# ElectronSheriff.net
KiCad netlist of a schematic drawn in EAGLE
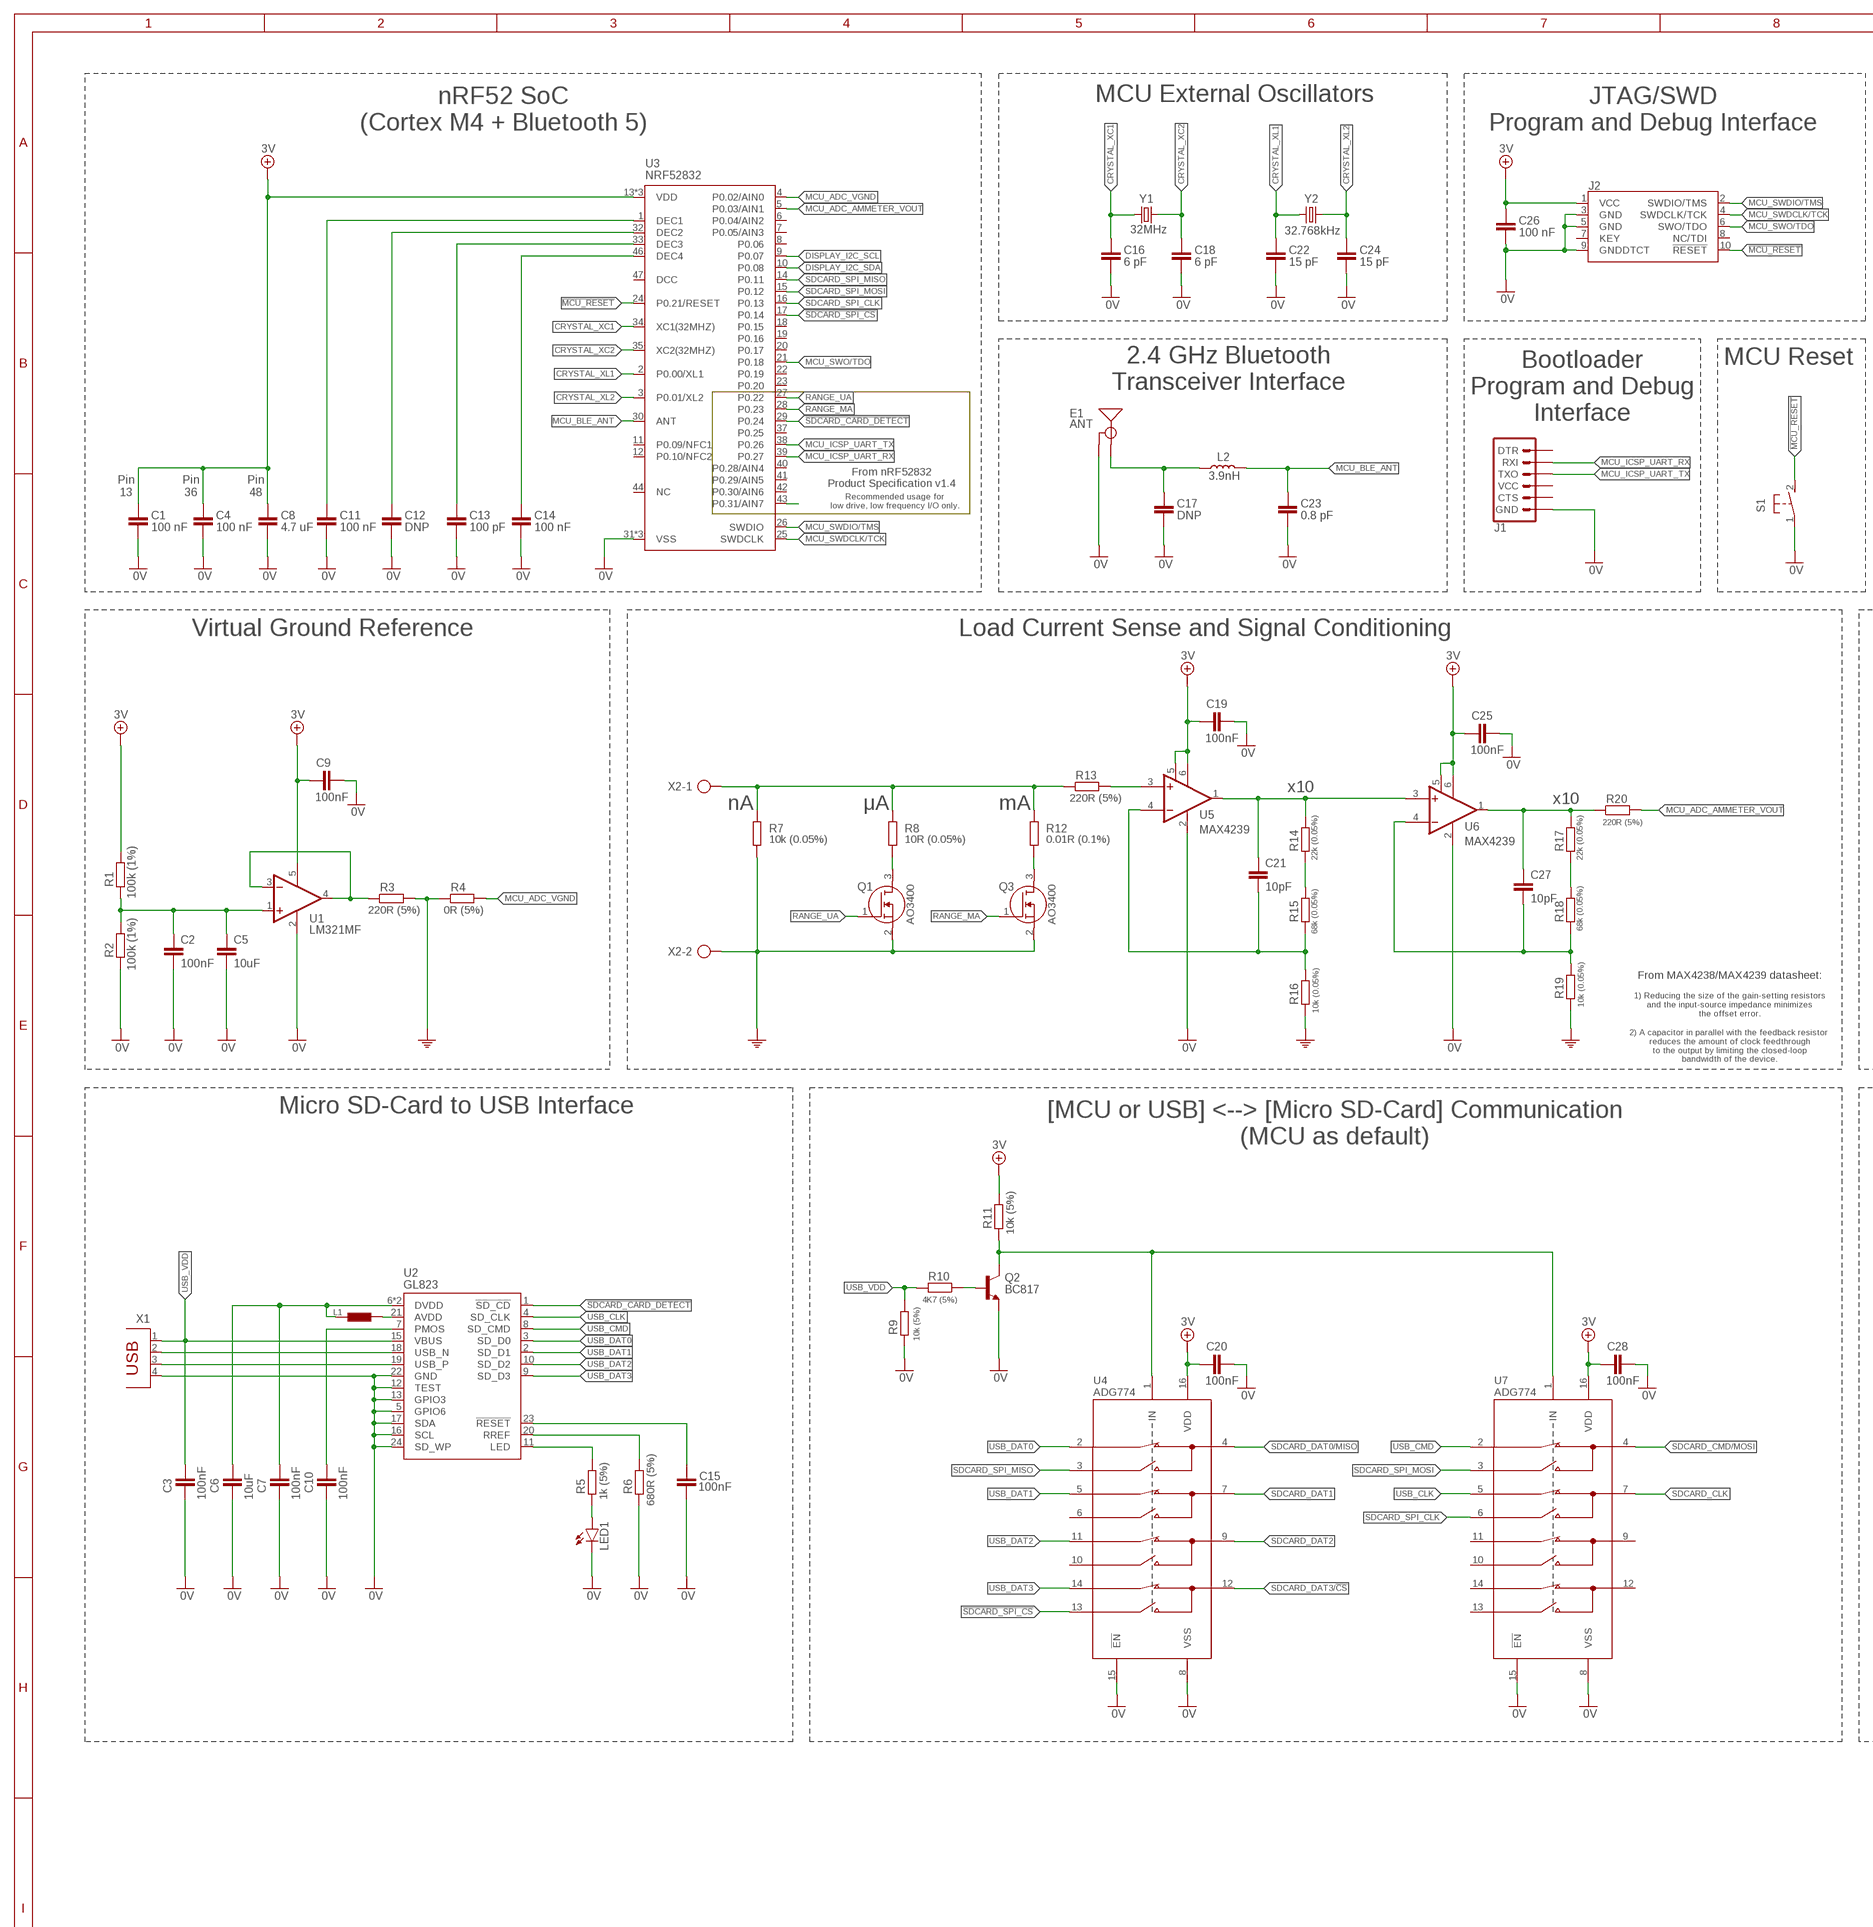
[diagram p0: schematic, sheet 1, part 1 of 2]
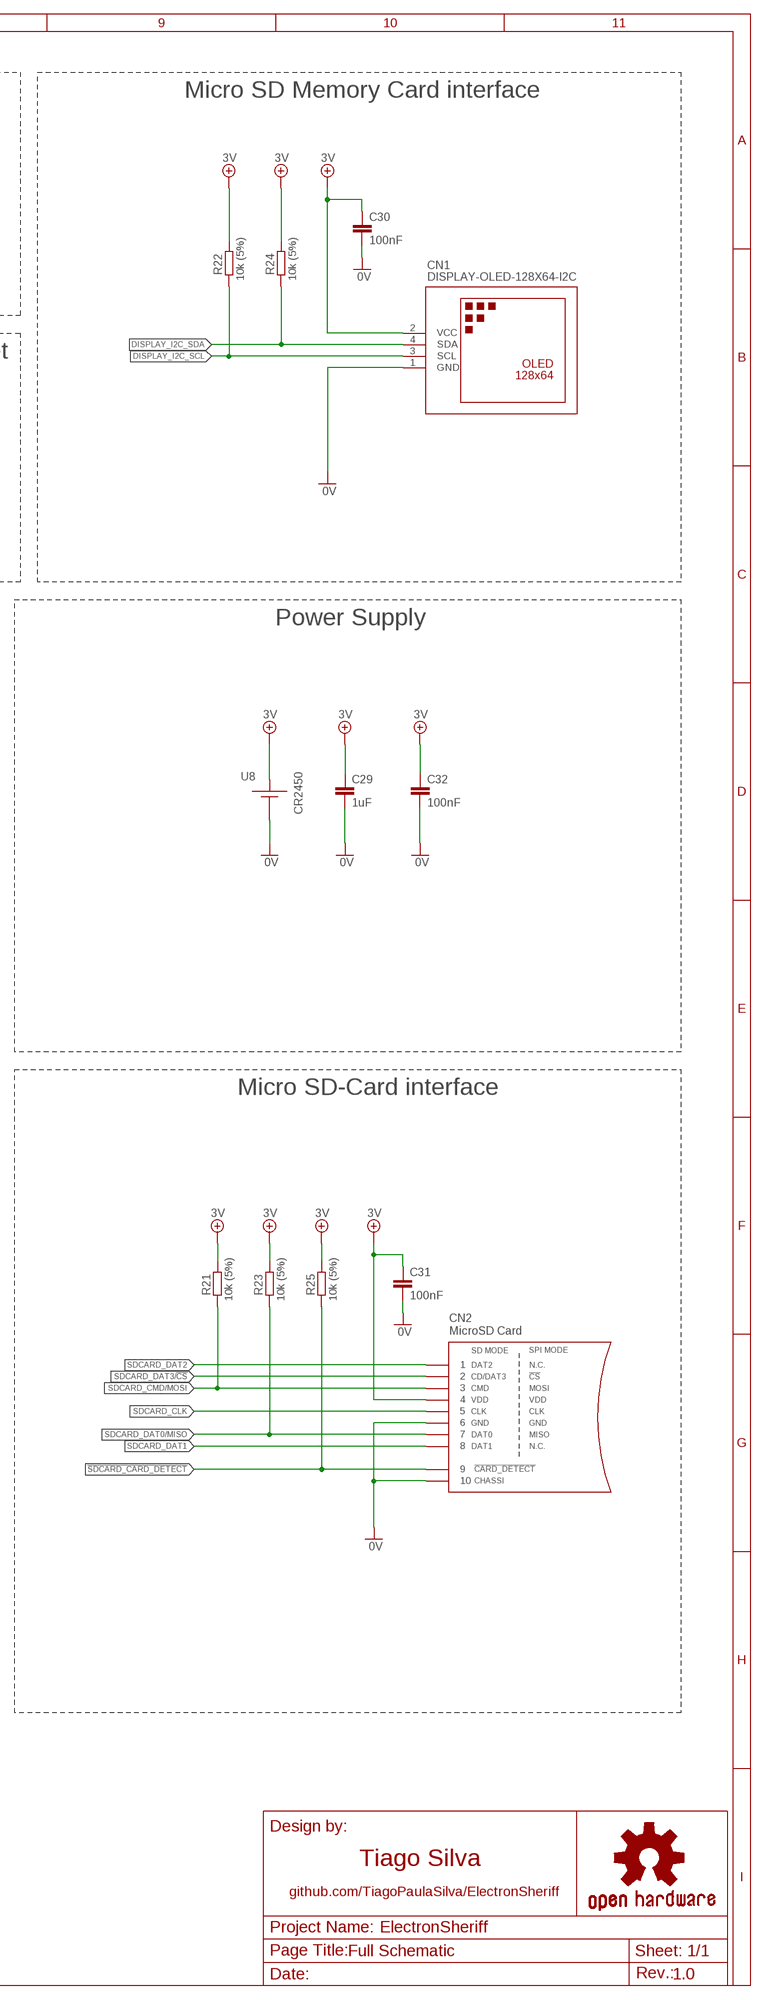
[diagram p1: schematic, sheet 1, part 2 of 2]

(export (version "E")
  (design (tool "Eeschema 10.0.6"))
  (components
    (comp (ref "C1")
      (value "100 nF")
      (footprint "eagle-import:C0603")
      (libsource (lib "eagle-import") (part "C-EUC0603"))
    )
    (comp (ref "C2")
      (value "100nF")
      (footprint "eagle-import:C0603")
      (libsource (lib "eagle-import") (part "C-EUC0603"))
    )
    (comp (ref "C3")
      (value "100nF")
      (footprint "eagle-import:C0603")
      (libsource (lib "eagle-import") (part "C-EUC0603"))
    )
    (comp (ref "C4")
      (value "100 nF")
      (footprint "eagle-import:C0603")
      (libsource (lib "eagle-import") (part "C-EUC0603"))
    )
    (comp (ref "C5")
      (value "10uF")
      (footprint "eagle-import:C0805")
      (libsource (lib "eagle-import") (part "C-EUC0805"))
    )
    (comp (ref "C6")
      (value "10uF")
      (footprint "eagle-import:C0603")
      (libsource (lib "eagle-import") (part "C-EUC0603"))
    )
    (comp (ref "C7")
      (value "100nF")
      (footprint "eagle-import:C0603")
      (libsource (lib "eagle-import") (part "C-EUC0603"))
    )
    (comp (ref "C8")
      (value "4.7 uF")
      (footprint "eagle-import:C0603")
      (libsource (lib "eagle-import") (part "C-EUC0603"))
    )
    (comp (ref "C9")
      (value "100nF")
      (footprint "eagle-import:C0603")
      (libsource (lib "eagle-import") (part "C-EUC0603"))
    )
    (comp (ref "C10")
      (value "100nF")
      (footprint "eagle-import:C0603")
      (libsource (lib "eagle-import") (part "C-EUC0603"))
    )
    (comp (ref "C11")
      (value "100 nF")
      (footprint "eagle-import:C0603")
      (libsource (lib "eagle-import") (part "C-EUC0603"))
    )
    (comp (ref "C12")
      (value "DNP")
      (footprint "eagle-import:C0603")
      (libsource (lib "eagle-import") (part "C-EUC0603"))
    )
    (comp (ref "C13")
      (value "100 pF")
      (footprint "eagle-import:C0603")
      (libsource (lib "eagle-import") (part "C-EUC0603"))
    )
    (comp (ref "C14")
      (value "100 nF")
      (footprint "eagle-import:C0603")
      (libsource (lib "eagle-import") (part "C-EUC0603"))
    )
    (comp (ref "C15")
      (value "100nF")
      (footprint "eagle-import:C0603")
      (libsource (lib "eagle-import") (part "C-EUC0603"))
    )
    (comp (ref "C16")
      (value "6 pF")
      (footprint "eagle-import:C0603")
      (libsource (lib "eagle-import") (part "C-EUC0603"))
    )
    (comp (ref "C17")
      (value "DNP")
      (footprint "eagle-import:C0603")
      (libsource (lib "eagle-import") (part "C-EUC0603"))
    )
    (comp (ref "C18")
      (value "6 pF")
      (footprint "eagle-import:C0603")
      (libsource (lib "eagle-import") (part "C-EUC0603"))
    )
    (comp (ref "C19")
      (value "100nF")
      (footprint "eagle-import:C0603")
      (libsource (lib "eagle-import") (part "C-EUC0603"))
    )
    (comp (ref "C20")
      (value "100nF")
      (footprint "eagle-import:C0603")
      (libsource (lib "eagle-import") (part "C-EUC0603"))
    )
    (comp (ref "C21")
      (value "10pF")
      (footprint "eagle-import:C0603")
      (libsource (lib "eagle-import") (part "C-EUC0603"))
    )
    (comp (ref "C22")
      (value "15 pF")
      (footprint "eagle-import:C0603")
      (libsource (lib "eagle-import") (part "C-EUC0603"))
    )
    (comp (ref "C23")
      (value "0.8 pF")
      (footprint "eagle-import:C0603")
      (libsource (lib "eagle-import") (part "C-EUC0603"))
    )
    (comp (ref "C24")
      (value "15 pF")
      (footprint "eagle-import:C0603")
      (libsource (lib "eagle-import") (part "C-EUC0603"))
    )
    (comp (ref "C25")
      (value "100nF")
      (footprint "eagle-import:C0603")
      (libsource (lib "eagle-import") (part "C-EUC0603"))
    )
    (comp (ref "C26")
      (value "100 nF")
      (footprint "eagle-import:C0603")
      (libsource (lib "eagle-import") (part "C-EUC0603"))
    )
    (comp (ref "C27")
      (value "10pF")
      (footprint "eagle-import:C0603")
      (libsource (lib "eagle-import") (part "C-EUC0603"))
    )
    (comp (ref "C28")
      (value "100nF")
      (footprint "eagle-import:C0603")
      (libsource (lib "eagle-import") (part "C-EUC0603"))
    )
    (comp (ref "C29")
      (value "1uF")
      (footprint "eagle-import:C0603")
      (libsource (lib "eagle-import") (part "C-EUC0603"))
    )
    (comp (ref "C30")
      (value "100nF")
      (footprint "eagle-import:C0603")
      (libsource (lib "eagle-import") (part "C-EUC0603"))
    )
    (comp (ref "C31")
      (value "100nF")
      (footprint "eagle-import:C0603")
      (libsource (lib "eagle-import") (part "C-EUC0603"))
    )
    (comp (ref "C32")
      (value "100nF")
      (footprint "eagle-import:C0603")
      (libsource (lib "eagle-import") (part "C-EUC0603"))
    )
    (comp (ref "CN1")
      (value "DISPLAY-OLED-128X64-I2C")
      (footprint "eagle-import:DISPLAY-OLED-128X64-I2C")
      (libsource (lib "eagle-import") (part "DISPLAY-OLED-128X64-I2C"))
    )
    (comp (ref "CN2")
      (value "MicroSD Card")
      (footprint "eagle-import:MICROSD-PUSH-OUT")
      (libsource (lib "eagle-import") (part "MICROSD-PUSH-OUT"))
    )
    (comp (ref "E1")
      (value "ANT")
      (footprint "eagle-import:TRACE_ANTENNA_2.4GHZ_15.2MM")
      (libsource (lib "eagle-import") (part "ANTENNA-GROUNDEDTRACE-15.2MM"))
    )
    (comp (ref "J1")
      (value "ARDUINO_SERIAL_PROGRAMPTH")
      (footprint "eagle-import:1X06")
      (libsource (lib "eagle-import") (part "ARDUINO_SERIAL_PROGRAMPTH"))
    )
    (comp (ref "J2")
      (value "CORTEX_DEBUGPTH")
      (footprint "eagle-import:2X5-PTH-1.27MM")
      (libsource (lib "eagle-import") (part "CORTEX_DEBUGPTH"))
    )
    (comp (ref "L1")
      (value "BLM15HB221SN1")
      (footprint "eagle-import:0402")
      (libsource (lib "eagle-import") (part "BLM15HB221SN1"))
    )
    (comp (ref "L2")
      (value "3.9nH")
      (footprint "eagle-import:0402")
      (libsource (lib "eagle-import") (part "INDUCTOR-0402-3.9NH"))
    )
    (comp (ref "LED1")
      (value "LEDCHIPLED_0603")
      (footprint "eagle-import:CHIPLED_0603")
      (libsource (lib "eagle-import") (part "LEDCHIPLED_0603"))
    )
    (comp (ref "Q1")
      (value "AO3400")
      (footprint "eagle-import:SOT95P280X125-3N")
      (libsource (lib "eagle-import") (part "AO3400"))
    )
    (comp (ref "Q2")
      (value "BC817")
      (footprint "eagle-import:SOT23-BEC")
      (libsource (lib "eagle-import") (part "BC817SMD-16LT1"))
    )
    (comp (ref "Q3")
      (value "AO3400")
      (footprint "eagle-import:SOT95P280X125-3N")
      (libsource (lib "eagle-import") (part "AO3400"))
    )
    (comp (ref "R1")
      (value "100k (1%)")
      (footprint "eagle-import:R0603")
      (libsource (lib "eagle-import") (part "R-EU_R0603"))
    )
    (comp (ref "R2")
      (value "100k (1%)")
      (footprint "eagle-import:R0603")
      (libsource (lib "eagle-import") (part "R-EU_R0603"))
    )
    (comp (ref "R3")
      (value "220R (5%)")
      (footprint "eagle-import:R0603")
      (libsource (lib "eagle-import") (part "R-EU_R0603"))
    )
    (comp (ref "R4")
      (value "0R (5%)")
      (footprint "eagle-import:R0603")
      (libsource (lib "eagle-import") (part "R-EU_R0603"))
    )
    (comp (ref "R5")
      (value "1k (5%)")
      (footprint "eagle-import:R0603")
      (libsource (lib "eagle-import") (part "R-EU_R0603"))
    )
    (comp (ref "R6")
      (value "680R (5%)")
      (footprint "eagle-import:R0603")
      (libsource (lib "eagle-import") (part "R-EU_R0603"))
    )
    (comp (ref "R7")
      (value "10k (0.05%)")
      (footprint "eagle-import:R0603")
      (libsource (lib "eagle-import") (part "R-EU_R0603"))
    )
    (comp (ref "R8")
      (value "10R (0.05%)")
      (footprint "eagle-import:R0603")
      (libsource (lib "eagle-import") (part "R-EU_R0603"))
    )
    (comp (ref "R9")
      (value "10k (5%)")
      (footprint "eagle-import:R0603")
      (libsource (lib "eagle-import") (part "R-EU_R0603"))
    )
    (comp (ref "R10")
      (value "4K7 (5%)")
      (footprint "eagle-import:R0603")
      (libsource (lib "eagle-import") (part "R-EU_R0603"))
    )
    (comp (ref "R11")
      (value "10k (5%)")
      (footprint "eagle-import:R0603")
      (libsource (lib "eagle-import") (part "R-EU_R0603"))
    )
    (comp (ref "R12")
      (value "0.01R (0.1%)")
      (footprint "eagle-import:R0603")
      (libsource (lib "eagle-import") (part "R-EU_R0603"))
    )
    (comp (ref "R13")
      (value "220R (5%)")
      (footprint "eagle-import:R0603")
      (libsource (lib "eagle-import") (part "R-EU_R0603"))
    )
    (comp (ref "R14")
      (value "22k (0.05%)")
      (footprint "eagle-import:R0603")
      (libsource (lib "eagle-import") (part "R-EU_R0603"))
    )
    (comp (ref "R15")
      (value "68k (0.05%)")
      (footprint "eagle-import:R0603")
      (libsource (lib "eagle-import") (part "R-EU_R0603"))
    )
    (comp (ref "R16")
      (value "10k (0.05%)")
      (footprint "eagle-import:R0603")
      (libsource (lib "eagle-import") (part "R-EU_R0603"))
    )
    (comp (ref "R17")
      (value "22k (0.05%)")
      (footprint "eagle-import:R0603")
      (libsource (lib "eagle-import") (part "R-EU_R0603"))
    )
    (comp (ref "R18")
      (value "68k (0.05%)")
      (footprint "eagle-import:R0603")
      (libsource (lib "eagle-import") (part "R-EU_R0603"))
    )
    (comp (ref "R19")
      (value "10k (0.05%)")
      (footprint "eagle-import:R0603")
      (libsource (lib "eagle-import") (part "R-EU_R0603"))
    )
    (comp (ref "R20")
      (value "220R (5%)")
      (footprint "eagle-import:R0603")
      (libsource (lib "eagle-import") (part "R-EU_R0603"))
    )
    (comp (ref "R21")
      (value "10k (5%)")
      (footprint "eagle-import:R0603")
      (libsource (lib "eagle-import") (part "R-EU_R0603"))
    )
    (comp (ref "R22")
      (value "10k (5%)")
      (footprint "eagle-import:R0603")
      (libsource (lib "eagle-import") (part "R-EU_R0603"))
    )
    (comp (ref "R23")
      (value "10k (5%)")
      (footprint "eagle-import:R0603")
      (libsource (lib "eagle-import") (part "R-EU_R0603"))
    )
    (comp (ref "R24")
      (value "10k (5%)")
      (footprint "eagle-import:R0603")
      (libsource (lib "eagle-import") (part "R-EU_R0603"))
    )
    (comp (ref "R25")
      (value "10k (5%)")
      (footprint "eagle-import:R0603")
      (libsource (lib "eagle-import") (part "R-EU_R0603"))
    )
    (comp (ref "S1")
      (value "DTSM-3")
      (footprint "eagle-import:DTSM-3")
      (libsource (lib "eagle-import") (part "DTSM-3"))
    )
    (comp (ref "U1")
      (value "LM321MF")
      (footprint "eagle-import:SOT23-5")
      (libsource (lib "eagle-import") (part "LM321?MF"))
    )
    (comp (ref "U2")
      (value "GL823")
      (footprint "eagle-import:SSOP24")
      (libsource (lib "eagle-import") (part "GL823(B)HG"))
    )
    (comp (ref "U3")
      (value "NRF52832")
      (footprint "eagle-import:QFN48-6X6MM")
      (libsource (lib "eagle-import") (part "NRF52832"))
    )
    (comp (ref "U4")
      (value "ADG774")
      (footprint "eagle-import:SOIC127P600X175-16N")
      (libsource (lib "eagle-import") (part "ADG774"))
    )
    (comp (ref "U5")
      (value "MAX4239")
      (footprint "eagle-import:SOT95P280X145-6N")
      (fields (field (name "MF") "Maxim Integrated") (field (name "MP") "MAX4239AUT+T"))
      (libsource (lib "eagle-import") (part "MAX4239AUTT"))
    )
    (comp (ref "U6")
      (value "MAX4239")
      (footprint "eagle-import:SOT95P280X145-6N")
      (fields (field (name "MF") "Maxim Integrated") (field (name "MP") "MAX4239AUT+T"))
      (libsource (lib "eagle-import") (part "MAX4239AUTT"))
    )
    (comp (ref "U7")
      (value "ADG774")
      (footprint "eagle-import:SOIC127P600X175-16N")
      (libsource (lib "eagle-import") (part "ADG774"))
    )
    (comp (ref "U8")
      (value "CR2450")
      (footprint "eagle-import:1053")
      (fields
        (field (name "MANUFACTURER_PART_NUMBER") "1053")
        (field (name "MOUSER_PART_NUMBER") "534-1053-BH")
      )
      (libsource (lib "eagle-import") (part "1053"))
    )
    (comp (ref "X1")
      (value "PN87520")
      (footprint "eagle-import:PN87520")
      (libsource (lib "eagle-import") (part "PN87520"))
    )
    (comp (ref "X2")
      (value "AK500/2-H")
      (footprint "eagle-import:AK500_2-H")
      (libsource (lib "eagle-import") (part "AK500/2-H"))
    )
    (comp (ref "Y1")
      (value "32MHz")
      (footprint "eagle-import:CRYSTAL-SMD-2.0X1.6MM")
      (libsource (lib "eagle-import") (part "CRYSTAL-32MHZ-SMD-2.0X1.6MM"))
    )
    (comp (ref "Y2")
      (value "32.768kHz")
      (footprint "eagle-import:CRYSTAL-SMD-3.2X1.5MM")
      (libsource (lib "eagle-import") (part "CRYSTAL-32.768KHZSMD-3.2X1.5"))
    )
  )
  (nets
    (net (code "1") (name "/SDCARD_DAT3{slash}~{CS}") (class "Default")
      (node (ref "CN2") (pin "2") (pinfunction "2_2") (pintype "bidirectional"))
      (node (ref "U4") (pin "12") (pinfunction "D4_12") (pintype "bidirectional"))
    )
    (net (code "2") (name "/~{MCU_RESET}") (class "Default")
      (node (ref "J2") (pin "10") (pinfunction "~{RESET}_10") (pintype "bidirectional"))
      (node (ref "S1") (pin "2") (pinfunction "2_2") (pintype "passive"))
      (node (ref "U3") (pin "24") (pinfunction "P0.21/RESET_24") (pintype "bidirectional"))
    )
    (net (code "3") (name "/~{SDCARD_CARD_DETECT}") (class "Default")
      (node (ref "CN2") (pin "9") (pinfunction "9_9") (pintype "bidirectional"))
      (node (ref "R25") (pin "1") (pinfunction "1_1") (pintype "passive"))
      (node (ref "U2") (pin "1") (pinfunction "~{SD_CD}_1") (pintype "input"))
      (node (ref "U3") (pin "29") (pinfunction "P0.24_29") (pintype "bidirectional"))
    )
    (net (code "4") (name "/~{SDCARD_SPI_CS}") (class "Default")
      (node (ref "U3") (pin "17") (pinfunction "P0.14_17") (pintype "bidirectional"))
      (node (ref "U4") (pin "13") (pinfunction "S4B_13") (pintype "bidirectional"))
    )
    (net (code "5") (name "0V") (class "Default")
      (node (ref "C1") (pin "2") (pinfunction "2_2") (pintype "passive"))
      (node (ref "C10") (pin "1") (pinfunction "1_1") (pintype "passive"))
      (node (ref "C11") (pin "2") (pinfunction "2_2") (pintype "passive"))
      (node (ref "C12") (pin "2") (pinfunction "2_2") (pintype "passive"))
      (node (ref "C13") (pin "2") (pinfunction "2_2") (pintype "passive"))
      (node (ref "C14") (pin "2") (pinfunction "2_2") (pintype "passive"))
      (node (ref "C15") (pin "1") (pinfunction "1_1") (pintype "passive"))
      (node (ref "C16") (pin "2") (pinfunction "2_2") (pintype "passive"))
      (node (ref "C17") (pin "2") (pinfunction "2_2") (pintype "passive"))
      (node (ref "C18") (pin "2") (pinfunction "2_2") (pintype "passive"))
      (node (ref "C19") (pin "2") (pinfunction "2_2") (pintype "passive"))
      (node (ref "C2") (pin "2") (pinfunction "2_2") (pintype "passive"))
      (node (ref "C20") (pin "2") (pinfunction "2_2") (pintype "passive"))
      (node (ref "C22") (pin "2") (pinfunction "2_2") (pintype "passive"))
      (node (ref "C23") (pin "2") (pinfunction "2_2") (pintype "passive"))
      (node (ref "C24") (pin "2") (pinfunction "2_2") (pintype "passive"))
      (node (ref "C25") (pin "2") (pinfunction "2_2") (pintype "passive"))
      (node (ref "C26") (pin "2") (pinfunction "2_2") (pintype "passive"))
      (node (ref "C28") (pin "2") (pinfunction "2_2") (pintype "passive"))
      (node (ref "C29") (pin "2") (pinfunction "2_2") (pintype "passive"))
      (node (ref "C3") (pin "1") (pinfunction "1_1") (pintype "passive"))
      (node (ref "C30") (pin "2") (pinfunction "2_2") (pintype "passive"))
      (node (ref "C31") (pin "2") (pinfunction "2_2") (pintype "passive"))
      (node (ref "C32") (pin "2") (pinfunction "2_2") (pintype "passive"))
      (node (ref "C4") (pin "2") (pinfunction "2_2") (pintype "passive"))
      (node (ref "C5") (pin "2") (pinfunction "2_2") (pintype "passive"))
      (node (ref "C6") (pin "1") (pinfunction "1_1") (pintype "passive"))
      (node (ref "C7") (pin "1") (pinfunction "1_1") (pintype "passive"))
      (node (ref "C8") (pin "2") (pinfunction "2_2") (pintype "passive"))
      (node (ref "C9") (pin "2") (pinfunction "2_2") (pintype "passive"))
      (node (ref "CN1") (pin "1") (pinfunction "GND_1") (pintype "power_in"))
      (node (ref "CN2") (pin "6") (pinfunction "6_6") (pintype "bidirectional"))
      (node (ref "CN2") (pin "G1") (pinfunction "10_G1") (pintype "bidirectional"))
      (node (ref "CN2") (pin "G2") (pinfunction "10_G2") (pintype "bidirectional"))
      (node (ref "CN2") (pin "G3") (pinfunction "10_G3") (pintype "bidirectional"))
      (node (ref "CN2") (pin "G4") (pinfunction "10_G4") (pintype "bidirectional"))
      (node (ref "E1") (pin "GND") (pinfunction "GND_GND") (pintype "bidirectional"))
      (node (ref "J1") (pin "6") (pinfunction "GND_6") (pintype "passive"))
      (node (ref "J2") (pin "3") (pinfunction "GND_3") (pintype "bidirectional"))
      (node (ref "J2") (pin "5") (pinfunction "GND_5") (pintype "bidirectional"))
      (node (ref "J2") (pin "9") (pinfunction "GNDDTCT_9") (pintype "bidirectional"))
      (node (ref "LED1") (pin "C") (pinfunction "C_C") (pintype "passive"))
      (node (ref "Q2") (pin "E") (pinfunction "E_E") (pintype "passive"))
      (node (ref "R2") (pin "1") (pinfunction "1_1") (pintype "passive"))
      (node (ref "R6") (pin "2") (pinfunction "2_2") (pintype "passive"))
      (node (ref "R9") (pin "2") (pinfunction "2_2") (pintype "passive"))
      (node (ref "S1") (pin "1") (pinfunction "1_1") (pintype "passive"))
      (node (ref "U1") (pin "2") (pinfunction "V-_2") (pintype "power_in"))
      (node (ref "U2") (pin "12") (pinfunction "TEST_12") (pintype "input"))
      (node (ref "U2") (pin "13") (pinfunction "GPIO3_13") (pintype "bidirectional"))
      (node (ref "U2") (pin "16") (pinfunction "SCL_16") (pintype "bidirectional"))
      (node (ref "U2") (pin "17") (pinfunction "SDA_17") (pintype "bidirectional"))
      (node (ref "U2") (pin "22") (pinfunction "GND_22") (pintype "power_in"))
      (node (ref "U2") (pin "24") (pinfunction "SD_WP_24") (pintype "input"))
      (node (ref "U2") (pin "5") (pinfunction "GPIO6_5") (pintype "bidirectional"))
      (node (ref "U3") (pin "31") (pinfunction "VSS_31") (pintype "bidirectional"))
      (node (ref "U3") (pin "45") (pinfunction "VSS_45") (pintype "bidirectional"))
      (node (ref "U3") (pin "EP") (pinfunction "VSS_EP") (pintype "bidirectional"))
      (node (ref "U4") (pin "15") (pinfunction "~{EN}_15") (pintype "bidirectional"))
      (node (ref "U4") (pin "8") (pinfunction "VSS_8") (pintype "bidirectional"))
      (node (ref "U5") (pin "2") (pinfunction "GND_2") (pintype "power_in"))
      (node (ref "U6") (pin "2") (pinfunction "GND_2") (pintype "power_in"))
      (node (ref "U7") (pin "15") (pinfunction "~{EN}_15") (pintype "bidirectional"))
      (node (ref "U7") (pin "8") (pinfunction "VSS_8") (pintype "bidirectional"))
      (node (ref "U8") (pin "1") (pinfunction "GND_1") (pintype "power_in"))
      (node (ref "X1") (pin "4") (pinfunction "4_4") (pintype "passive"))
    )
    (net (code "6") (name "3V") (class "Default")
      (node (ref "C1") (pin "1") (pinfunction "1_1") (pintype "passive"))
      (node (ref "C19") (pin "1") (pinfunction "1_1") (pintype "passive"))
      (node (ref "C20") (pin "1") (pinfunction "1_1") (pintype "passive"))
      (node (ref "C25") (pin "1") (pinfunction "1_1") (pintype "passive"))
      (node (ref "C26") (pin "1") (pinfunction "1_1") (pintype "passive"))
      (node (ref "C28") (pin "1") (pinfunction "1_1") (pintype "passive"))
      (node (ref "C29") (pin "1") (pinfunction "1_1") (pintype "passive"))
      (node (ref "C30") (pin "1") (pinfunction "1_1") (pintype "passive"))
      (node (ref "C31") (pin "1") (pinfunction "1_1") (pintype "passive"))
      (node (ref "C32") (pin "1") (pinfunction "1_1") (pintype "passive"))
      (node (ref "C4") (pin "1") (pinfunction "1_1") (pintype "passive"))
      (node (ref "C8") (pin "1") (pinfunction "1_1") (pintype "passive"))
      (node (ref "C9") (pin "1") (pinfunction "1_1") (pintype "passive"))
      (node (ref "CN1") (pin "2") (pinfunction "VCC_2") (pintype "power_in"))
      (node (ref "CN2") (pin "4") (pinfunction "4_4") (pintype "bidirectional"))
      (node (ref "J2") (pin "1") (pinfunction "VCC_1") (pintype "bidirectional"))
      (node (ref "R1") (pin "2") (pinfunction "2_2") (pintype "passive"))
      (node (ref "R11") (pin "2") (pinfunction "2_2") (pintype "passive"))
      (node (ref "R21") (pin "2") (pinfunction "2_2") (pintype "passive"))
      (node (ref "R22") (pin "2") (pinfunction "2_2") (pintype "passive"))
      (node (ref "R23") (pin "2") (pinfunction "2_2") (pintype "passive"))
      (node (ref "R24") (pin "2") (pinfunction "2_2") (pintype "passive"))
      (node (ref "R25") (pin "2") (pinfunction "2_2") (pintype "passive"))
      (node (ref "U1") (pin "5") (pinfunction "V+_5") (pintype "power_in"))
      (node (ref "U3") (pin "13") (pinfunction "VDD_13") (pintype "bidirectional"))
      (node (ref "U3") (pin "36") (pinfunction "VDD_36") (pintype "bidirectional"))
      (node (ref "U3") (pin "48") (pinfunction "VDD_48") (pintype "bidirectional"))
      (node (ref "U4") (pin "16") (pinfunction "VDD_16") (pintype "bidirectional"))
      (node (ref "U5") (pin "5") (pinfunction "~{SHDN}_5") (pintype "input"))
      (node (ref "U5") (pin "6") (pinfunction "VCC_6") (pintype "power_in"))
      (node (ref "U6") (pin "5") (pinfunction "~{SHDN}_5") (pintype "input"))
      (node (ref "U6") (pin "6") (pinfunction "VCC_6") (pintype "power_in"))
      (node (ref "U7") (pin "16") (pinfunction "VDD_16") (pintype "bidirectional"))
      (node (ref "U8") (pin "2") (pinfunction "3V_2") (pintype "power_in"))
    )
    (net (code "7") (name "CRYSTAL_XC1") (class "Default")
      (node (ref "C16") (pin "1") (pinfunction "1_1") (pintype "passive"))
      (node (ref "U3") (pin "34") (pinfunction "XC1(32MHZ)_34") (pintype "bidirectional"))
      (node (ref "Y1") (pin "3") (pinfunction "2_3") (pintype "passive"))
    )
    (net (code "8") (name "CRYSTAL_XC2") (class "Default")
      (node (ref "C18") (pin "1") (pinfunction "1_1") (pintype "passive"))
      (node (ref "U3") (pin "35") (pinfunction "XC2(32MHZ)_35") (pintype "bidirectional"))
      (node (ref "Y1") (pin "1") (pinfunction "1_1") (pintype "passive"))
    )
    (net (code "9") (name "CRYSTAL_XL1") (class "Default")
      (node (ref "C22") (pin "1") (pinfunction "1_1") (pintype "passive"))
      (node (ref "U3") (pin "2") (pinfunction "P0.00/XL1_2") (pintype "bidirectional"))
      (node (ref "Y2") (pin "P$2") (pinfunction "2_P$2") (pintype "passive"))
    )
    (net (code "10") (name "CRYSTAL_XL2") (class "Default")
      (node (ref "C24") (pin "1") (pinfunction "1_1") (pintype "passive"))
      (node (ref "U3") (pin "3") (pinfunction "P0.01/XL2_3") (pintype "bidirectional"))
      (node (ref "Y2") (pin "P$1") (pinfunction "1_P$1") (pintype "passive"))
    )
    (net (code "11") (name "DISPLAY_I2C_SCL") (class "Default")
      (node (ref "CN1") (pin "3") (pinfunction "SCL_3") (pintype "bidirectional"))
      (node (ref "R22") (pin "1") (pinfunction "1_1") (pintype "passive"))
      (node (ref "U3") (pin "9") (pinfunction "P0.07_9") (pintype "bidirectional"))
    )
    (net (code "12") (name "DISPLAY_I2C_SDA") (class "Default")
      (node (ref "CN1") (pin "4") (pinfunction "SDA_4") (pintype "bidirectional"))
      (node (ref "R24") (pin "1") (pinfunction "1_1") (pintype "passive"))
      (node (ref "U3") (pin "10") (pinfunction "P0.08_10") (pintype "bidirectional"))
    )
    (net (code "13") (name "MCU_ADC_AMMETER_VOUT") (class "Default")
      (node (ref "R20") (pin "2") (pinfunction "2_2") (pintype "passive"))
      (node (ref "U3") (pin "5") (pinfunction "P0.03/AIN1_5") (pintype "bidirectional"))
    )
    (net (code "14") (name "MCU_ADC_VGND") (class "Default")
      (node (ref "R4") (pin "2") (pinfunction "2_2") (pintype "passive"))
      (node (ref "U3") (pin "4") (pinfunction "P0.02/AIN0_4") (pintype "bidirectional"))
    )
    (net (code "15") (name "MCU_BLE_ANT") (class "Default")
      (node (ref "C23") (pin "1") (pinfunction "1_1") (pintype "passive"))
      (node (ref "L2") (pin "2") (pinfunction "2_2") (pintype "passive"))
      (node (ref "U3") (pin "30") (pinfunction "ANT_30") (pintype "bidirectional"))
    )
    (net (code "16") (name "MCU_ICSP_UART_RX") (class "Default")
      (node (ref "J1") (pin "2") (pinfunction "RXI_2") (pintype "passive"))
      (node (ref "U3") (pin "39") (pinfunction "P0.27_39") (pintype "bidirectional"))
    )
    (net (code "17") (name "MCU_ICSP_UART_TX") (class "Default")
      (node (ref "J1") (pin "3") (pinfunction "TXO_3") (pintype "passive"))
      (node (ref "U3") (pin "38") (pinfunction "P0.26_38") (pintype "bidirectional"))
    )
    (net (code "18") (name "MCU_SWDCLK{slash}TCK") (class "Default")
      (node (ref "J2") (pin "4") (pinfunction "SWDCLK/TCK_4") (pintype "bidirectional"))
      (node (ref "U3") (pin "25") (pinfunction "SWDCLK_25") (pintype "bidirectional"))
    )
    (net (code "19") (name "MCU_SWDIO{slash}TMS") (class "Default")
      (node (ref "J2") (pin "2") (pinfunction "SWDIO/TMS_2") (pintype "bidirectional"))
      (node (ref "U3") (pin "26") (pinfunction "SWDIO_26") (pintype "bidirectional"))
    )
    (net (code "20") (name "MCU_SWO{slash}TDO") (class "Default")
      (node (ref "J2") (pin "6") (pinfunction "SWO/TDO_6") (pintype "bidirectional"))
      (node (ref "U3") (pin "21") (pinfunction "P0.18_21") (pintype "bidirectional"))
    )
    (net (code "21") (name "Net-(C6-Pad2)") (class "Default")
      (node (ref "C6") (pin "2") (pinfunction "2_2") (pintype "passive"))
      (node (ref "C7") (pin "2") (pinfunction "2_2") (pintype "passive"))
      (node (ref "L1") (pin "1") (pinfunction "1_1") (pintype "passive"))
      (node (ref "U2") (pin "14") (pinfunction "DVDD_14") (pintype "power_in"))
      (node (ref "U2") (pin "6") (pinfunction "DVDD_6") (pintype "power_in"))
    )
    (net (code "22") (name "Net-(E1-SIGNAL)") (class "Default")
      (node (ref "C17") (pin "1") (pinfunction "1_1") (pintype "passive"))
      (node (ref "E1") (pin "ANT") (pinfunction "SIGNAL_ANT") (pintype "bidirectional"))
      (node (ref "L2") (pin "1") (pinfunction "1_1") (pintype "passive"))
    )
    (net (code "23") (name "Net-(LED1-PadA)") (class "Default")
      (node (ref "LED1") (pin "A") (pinfunction "A_A") (pintype "passive"))
      (node (ref "R5") (pin "2") (pinfunction "2_2") (pintype "passive"))
    )
    (net (code "24") (name "Net-(Q1-D)") (class "Default")
      (node (ref "Q1") (pin "3") (pinfunction "D_3") (pintype "bidirectional"))
      (node (ref "R8") (pin "1") (pinfunction "1_1") (pintype "passive"))
    )
    (net (code "25") (name "Net-(Q2-PadB)") (class "Default")
      (node (ref "Q2") (pin "B") (pinfunction "B_B") (pintype "passive"))
      (node (ref "R10") (pin "1") (pinfunction "1_1") (pintype "passive"))
    )
    (net (code "26") (name "Net-(Q3-D)") (class "Default")
      (node (ref "Q3") (pin "3") (pinfunction "D_3") (pintype "bidirectional"))
      (node (ref "R12") (pin "1") (pinfunction "1_1") (pintype "passive"))
    )
    (net (code "27") (name "Net-(R14-Pad1)") (class "Default")
      (node (ref "R14") (pin "1") (pinfunction "1_1") (pintype "passive"))
      (node (ref "R15") (pin "2") (pinfunction "2_2") (pintype "passive"))
    )
    (net (code "28") (name "Net-(R17-Pad1)") (class "Default")
      (node (ref "R17") (pin "1") (pinfunction "1_1") (pintype "passive"))
      (node (ref "R18") (pin "2") (pinfunction "2_2") (pintype "passive"))
    )
    (net (code "29") (name "Net-(U1-+IN)") (class "Default")
      (node (ref "C2") (pin "1") (pinfunction "1_1") (pintype "passive"))
      (node (ref "C5") (pin "1") (pinfunction "1_1") (pintype "passive"))
      (node (ref "R1") (pin "1") (pinfunction "1_1") (pintype "passive"))
      (node (ref "R2") (pin "2") (pinfunction "2_2") (pintype "passive"))
      (node (ref "U1") (pin "1") (pinfunction "+IN_1") (pintype "input"))
    )
    (net (code "30") (name "Net-(U1--IN)") (class "Default")
      (node (ref "R3") (pin "1") (pinfunction "1_1") (pintype "passive"))
      (node (ref "U1") (pin "3") (pinfunction "-IN_3") (pintype "input"))
      (node (ref "U1") (pin "4") (pinfunction "OUT_4") (pintype "output"))
    )
    (net (code "31") (name "Net-(U2-AVDD)") (class "Default")
      (node (ref "L1") (pin "2") (pinfunction "2_2") (pintype "passive"))
      (node (ref "U2") (pin "21") (pinfunction "AVDD_21") (pintype "power_in"))
    )
    (net (code "32") (name "Net-(U2-LED)") (class "Default")
      (node (ref "R5") (pin "1") (pinfunction "1_1") (pintype "passive"))
      (node (ref "U2") (pin "11") (pinfunction "LED_11") (pintype "output"))
    )
    (net (code "33") (name "Net-(U2-PMOS)") (class "Default")
      (node (ref "C10") (pin "2") (pinfunction "2_2") (pintype "passive"))
      (node (ref "U2") (pin "7") (pinfunction "PMOS_7") (pintype "power_in"))
    )
    (net (code "34") (name "Net-(U2-RREF)") (class "Default")
      (node (ref "R6") (pin "1") (pinfunction "1_1") (pintype "passive"))
      (node (ref "U2") (pin "20") (pinfunction "RREF_20") (pintype "bidirectional"))
    )
    (net (code "35") (name "Net-(U2-USB_N)") (class "Default")
      (node (ref "U2") (pin "18") (pinfunction "USB_N_18") (pintype "bidirectional"))
      (node (ref "X1") (pin "2") (pinfunction "2_2") (pintype "passive"))
    )
    (net (code "36") (name "Net-(U2-USB_P)") (class "Default")
      (node (ref "U2") (pin "19") (pinfunction "USB_P_19") (pintype "bidirectional"))
      (node (ref "X1") (pin "3") (pinfunction "3_3") (pintype "passive"))
    )
    (net (code "37") (name "Net-(U2-~{RESET})") (class "Default")
      (node (ref "C15") (pin "2") (pinfunction "2_2") (pintype "passive"))
      (node (ref "U2") (pin "23") (pinfunction "~{RESET}_23") (pintype "input"))
    )
    (net (code "38") (name "Net-(U3-DEC1)") (class "Default")
      (node (ref "C11") (pin "1") (pinfunction "1_1") (pintype "passive"))
      (node (ref "U3") (pin "1") (pinfunction "DEC1_1") (pintype "bidirectional"))
    )
    (net (code "39") (name "Net-(U3-DEC2)") (class "Default")
      (node (ref "C12") (pin "1") (pinfunction "1_1") (pintype "passive"))
      (node (ref "U3") (pin "32") (pinfunction "DEC2_32") (pintype "bidirectional"))
    )
    (net (code "40") (name "Net-(U3-DEC3)") (class "Default")
      (node (ref "C13") (pin "1") (pinfunction "1_1") (pintype "passive"))
      (node (ref "U3") (pin "33") (pinfunction "DEC3_33") (pintype "bidirectional"))
    )
    (net (code "41") (name "Net-(U3-DEC4)") (class "Default")
      (node (ref "C14") (pin "1") (pinfunction "1_1") (pintype "passive"))
      (node (ref "U3") (pin "46") (pinfunction "DEC4_46") (pintype "bidirectional"))
    )
    (net (code "42") (name "Net-(U4-IN)") (class "Default")
      (node (ref "Q2") (pin "C") (pinfunction "C_C") (pintype "passive"))
      (node (ref "R11") (pin "1") (pinfunction "1_1") (pintype "passive"))
      (node (ref "U4") (pin "1") (pinfunction "IN_1") (pintype "bidirectional"))
      (node (ref "U7") (pin "1") (pinfunction "IN_1") (pintype "bidirectional"))
    )
    (net (code "43") (name "Net-(U5-IN+)") (class "Default")
      (node (ref "R13") (pin "2") (pinfunction "2_2") (pintype "passive"))
      (node (ref "U5") (pin "3") (pinfunction "IN+_3") (pintype "input"))
    )
    (net (code "44") (name "Net-(U5-IN-)") (class "Default")
      (node (ref "C21") (pin "2") (pinfunction "2_2") (pintype "passive"))
      (node (ref "R15") (pin "1") (pinfunction "1_1") (pintype "passive"))
      (node (ref "R16") (pin "2") (pinfunction "2_2") (pintype "passive"))
      (node (ref "U5") (pin "4") (pinfunction "IN-_4") (pintype "input"))
    )
    (net (code "45") (name "Net-(U5-OUT)") (class "Default")
      (node (ref "C21") (pin "1") (pinfunction "1_1") (pintype "passive"))
      (node (ref "R14") (pin "2") (pinfunction "2_2") (pintype "passive"))
      (node (ref "U5") (pin "1") (pinfunction "OUT_1") (pintype "output"))
      (node (ref "U6") (pin "3") (pinfunction "IN+_3") (pintype "input"))
    )
    (net (code "46") (name "Net-(U6-IN-)") (class "Default")
      (node (ref "C27") (pin "2") (pinfunction "2_2") (pintype "passive"))
      (node (ref "R18") (pin "1") (pinfunction "1_1") (pintype "passive"))
      (node (ref "R19") (pin "2") (pinfunction "2_2") (pintype "passive"))
      (node (ref "U6") (pin "4") (pinfunction "IN-_4") (pintype "input"))
    )
    (net (code "47") (name "Net-(U6-OUT)") (class "Default")
      (node (ref "C27") (pin "1") (pinfunction "1_1") (pintype "passive"))
      (node (ref "R17") (pin "2") (pinfunction "2_2") (pintype "passive"))
      (node (ref "R20") (pin "1") (pinfunction "1_1") (pintype "passive"))
      (node (ref "U6") (pin "1") (pinfunction "OUT_1") (pintype "output"))
    )
    (net (code "48") (name "Net-(X2A-KL)") (class "Default")
      (node (ref "R12") (pin "2") (pinfunction "2_2") (pintype "passive"))
      (node (ref "R13") (pin "1") (pinfunction "1_1") (pintype "passive"))
      (node (ref "R7") (pin "2") (pinfunction "2_2") (pintype "passive"))
      (node (ref "R8") (pin "2") (pinfunction "2_2") (pintype "passive"))
      (node (ref "X2") (pin "1") (pinfunction "KL_1") (pintype "passive"))
    )
    (net (code "49") (name "PE") (class "Default")
      (node (ref "Q1") (pin "2") (pinfunction "S_2") (pintype "bidirectional"))
      (node (ref "Q3") (pin "2") (pinfunction "S_2") (pintype "bidirectional"))
      (node (ref "R16") (pin "1") (pinfunction "1_1") (pintype "passive"))
      (node (ref "R19") (pin "1") (pinfunction "1_1") (pintype "passive"))
      (node (ref "R3") (pin "2") (pinfunction "2_2") (pintype "passive"))
      (node (ref "R4") (pin "1") (pinfunction "1_1") (pintype "passive"))
      (node (ref "R7") (pin "1") (pinfunction "1_1") (pintype "passive"))
      (node (ref "X2") (pin "2") (pinfunction "KL_2") (pintype "passive"))
    )
    (net (code "50") (name "RANGE_MA") (class "Default")
      (node (ref "Q3") (pin "1") (pinfunction "G_1") (pintype "bidirectional"))
      (node (ref "U3") (pin "28") (pinfunction "P0.23_28") (pintype "bidirectional"))
    )
    (net (code "51") (name "RANGE_UA") (class "Default")
      (node (ref "Q1") (pin "1") (pinfunction "G_1") (pintype "bidirectional"))
      (node (ref "U3") (pin "27") (pinfunction "P0.22_27") (pintype "bidirectional"))
    )
    (net (code "52") (name "SDCARD_CLK") (class "Default")
      (node (ref "CN2") (pin "5") (pinfunction "5_5") (pintype "bidirectional"))
      (node (ref "U7") (pin "7") (pinfunction "D2_7") (pintype "bidirectional"))
    )
    (net (code "53") (name "SDCARD_CMD{slash}MOSI") (class "Default")
      (node (ref "CN2") (pin "3") (pinfunction "3_3") (pintype "bidirectional"))
      (node (ref "R21") (pin "1") (pinfunction "1_1") (pintype "passive"))
      (node (ref "U7") (pin "4") (pinfunction "D1_4") (pintype "bidirectional"))
    )
    (net (code "54") (name "SDCARD_DAT0{slash}MISO") (class "Default")
      (node (ref "CN2") (pin "7") (pinfunction "7_7") (pintype "bidirectional"))
      (node (ref "R23") (pin "1") (pinfunction "1_1") (pintype "passive"))
      (node (ref "U4") (pin "4") (pinfunction "D1_4") (pintype "bidirectional"))
    )
    (net (code "55") (name "SDCARD_DAT1") (class "Default")
      (node (ref "CN2") (pin "8") (pinfunction "8_8") (pintype "bidirectional"))
      (node (ref "U4") (pin "7") (pinfunction "D2_7") (pintype "bidirectional"))
    )
    (net (code "56") (name "SDCARD_DAT2") (class "Default")
      (node (ref "CN2") (pin "1") (pinfunction "1_1") (pintype "bidirectional"))
      (node (ref "U4") (pin "9") (pinfunction "D3_9") (pintype "bidirectional"))
    )
    (net (code "57") (name "SDCARD_SPI_CLK") (class "Default")
      (node (ref "U3") (pin "16") (pinfunction "P0.13_16") (pintype "bidirectional"))
      (node (ref "U7") (pin "6") (pinfunction "S2B_6") (pintype "bidirectional"))
    )
    (net (code "58") (name "SDCARD_SPI_MISO") (class "Default")
      (node (ref "U3") (pin "14") (pinfunction "P0.11_14") (pintype "bidirectional"))
      (node (ref "U4") (pin "3") (pinfunction "S1B_3") (pintype "bidirectional"))
    )
    (net (code "59") (name "SDCARD_SPI_MOSI") (class "Default")
      (node (ref "U3") (pin "15") (pinfunction "P0.12_15") (pintype "bidirectional"))
      (node (ref "U7") (pin "3") (pinfunction "S1B_3") (pintype "bidirectional"))
    )
    (net (code "60") (name "USB_CLK") (class "Default")
      (node (ref "U2") (pin "4") (pinfunction "SD_CLK_4") (pintype "output"))
      (node (ref "U7") (pin "5") (pinfunction "S2A_5") (pintype "bidirectional"))
    )
    (net (code "61") (name "USB_CMD") (class "Default")
      (node (ref "U2") (pin "8") (pinfunction "SD_CMD_8") (pintype "bidirectional"))
      (node (ref "U7") (pin "2") (pinfunction "S1A_2") (pintype "bidirectional"))
    )
    (net (code "62") (name "USB_DAT0") (class "Default")
      (node (ref "U2") (pin "3") (pinfunction "SD_D0_3") (pintype "bidirectional"))
      (node (ref "U4") (pin "2") (pinfunction "S1A_2") (pintype "bidirectional"))
    )
    (net (code "63") (name "USB_DAT1") (class "Default")
      (node (ref "U2") (pin "2") (pinfunction "SD_D1_2") (pintype "bidirectional"))
      (node (ref "U4") (pin "5") (pinfunction "S2A_5") (pintype "bidirectional"))
    )
    (net (code "64") (name "USB_DAT2") (class "Default")
      (node (ref "U2") (pin "10") (pinfunction "SD_D2_10") (pintype "bidirectional"))
      (node (ref "U4") (pin "11") (pinfunction "S3A_11") (pintype "bidirectional"))
    )
    (net (code "65") (name "USB_DAT3") (class "Default")
      (node (ref "U2") (pin "9") (pinfunction "SD_D3_9") (pintype "bidirectional"))
      (node (ref "U4") (pin "14") (pinfunction "S4A_14") (pintype "bidirectional"))
    )
    (net (code "66") (name "USB_VDD") (class "Default")
      (node (ref "C3") (pin "2") (pinfunction "2_2") (pintype "passive"))
      (node (ref "R10") (pin "2") (pinfunction "2_2") (pintype "passive"))
      (node (ref "R9") (pin "1") (pinfunction "1_1") (pintype "passive"))
      (node (ref "U2") (pin "15") (pinfunction "VBUS_15") (pintype "power_in"))
      (node (ref "X1") (pin "1") (pinfunction "1_1") (pintype "passive"))
    )
    (net (code "67") (name "unconnected-(J1-CTS-Pad5)") (class "Default")
      (node (ref "J1") (pin "5") (pinfunction "CTS_5") (pintype "passive"))
    )
    (net (code "68") (name "unconnected-(J1-DTR-Pad1)") (class "Default")
      (node (ref "J1") (pin "1") (pinfunction "DTR_1") (pintype "passive"))
    )
    (net (code "69") (name "unconnected-(J1-VCC-Pad4)") (class "Default")
      (node (ref "J1") (pin "4") (pinfunction "VCC_4") (pintype "passive"))
    )
    (net (code "70") (name "unconnected-(J2-KEY-Pad7)") (class "Default")
      (node (ref "J2") (pin "7") (pinfunction "KEY_7") (pintype "bidirectional"))
    )
    (net (code "71") (name "unconnected-(J2-NC{slash}TDI-Pad8)") (class "Default")
      (node (ref "J2") (pin "8") (pinfunction "NC/TDI_8") (pintype "bidirectional"))
    )
    (net (code "72") (name "unconnected-(U3-DCC-Pad47)") (class "Default")
      (node (ref "U3") (pin "47") (pinfunction "DCC_47") (pintype "bidirectional"))
    )
    (net (code "73") (name "unconnected-(U3-NC-Pad44)") (class "Default")
      (node (ref "U3") (pin "44") (pinfunction "NC_44") (pintype "bidirectional"))
    )
    (net (code "74") (name "unconnected-(U3-P0.04{slash}AIN2-Pad6)") (class "Default")
      (node (ref "U3") (pin "6") (pinfunction "P0.04/AIN2_6") (pintype "bidirectional"))
    )
    (net (code "75") (name "unconnected-(U3-P0.05{slash}AIN3-Pad7)") (class "Default")
      (node (ref "U3") (pin "7") (pinfunction "P0.05/AIN3_7") (pintype "bidirectional"))
    )
    (net (code "76") (name "unconnected-(U3-P0.06-Pad8)") (class "Default")
      (node (ref "U3") (pin "8") (pinfunction "P0.06_8") (pintype "bidirectional"))
    )
    (net (code "77") (name "unconnected-(U3-P0.09{slash}NFC1-Pad11)") (class "Default")
      (node (ref "U3") (pin "11") (pinfunction "P0.09/NFC1_11") (pintype "bidirectional"))
    )
    (net (code "78") (name "unconnected-(U3-P0.10{slash}NFC2-Pad12)") (class "Default")
      (node (ref "U3") (pin "12") (pinfunction "P0.10/NFC2_12") (pintype "bidirectional"))
    )
    (net (code "79") (name "unconnected-(U3-P0.15-Pad18)") (class "Default")
      (node (ref "U3") (pin "18") (pinfunction "P0.15_18") (pintype "bidirectional"))
    )
    (net (code "80") (name "unconnected-(U3-P0.16-Pad19)") (class "Default")
      (node (ref "U3") (pin "19") (pinfunction "P0.16_19") (pintype "bidirectional"))
    )
    (net (code "81") (name "unconnected-(U3-P0.17-Pad20)") (class "Default")
      (node (ref "U3") (pin "20") (pinfunction "P0.17_20") (pintype "bidirectional"))
    )
    (net (code "82") (name "unconnected-(U3-P0.19-Pad22)") (class "Default")
      (node (ref "U3") (pin "22") (pinfunction "P0.19_22") (pintype "bidirectional"))
    )
    (net (code "83") (name "unconnected-(U3-P0.20-Pad23)") (class "Default")
      (node (ref "U3") (pin "23") (pinfunction "P0.20_23") (pintype "bidirectional"))
    )
    (net (code "84") (name "unconnected-(U3-P0.25-Pad37)") (class "Default")
      (node (ref "U3") (pin "37") (pinfunction "P0.25_37") (pintype "bidirectional"))
    )
    (net (code "85") (name "unconnected-(U3-P0.28{slash}AIN4-Pad40)") (class "Default")
      (node (ref "U3") (pin "40") (pinfunction "P0.28/AIN4_40") (pintype "bidirectional"))
    )
    (net (code "86") (name "unconnected-(U3-P0.29{slash}AIN5-Pad41)") (class "Default")
      (node (ref "U3") (pin "41") (pinfunction "P0.29/AIN5_41") (pintype "bidirectional"))
    )
    (net (code "87") (name "unconnected-(U3-P0.30{slash}AIN6-Pad42)") (class "Default")
      (node (ref "U3") (pin "42") (pinfunction "P0.30/AIN6_42") (pintype "bidirectional"))
    )
    (net (code "88") (name "unconnected-(U3-P0.31{slash}AIN7-Pad43)") (class "Default")
      (node (ref "U3") (pin "43") (pinfunction "P0.31/AIN7_43") (pintype "bidirectional"))
    )
    (net (code "89") (name "unconnected-(U4-S2B-Pad6)") (class "Default")
      (node (ref "U4") (pin "6") (pinfunction "S2B_6") (pintype "bidirectional"))
    )
    (net (code "90") (name "unconnected-(U4-S3B-Pad10)") (class "Default")
      (node (ref "U4") (pin "10") (pinfunction "S3B_10") (pintype "bidirectional"))
    )
    (net (code "91") (name "unconnected-(U7-D3-Pad9)") (class "Default")
      (node (ref "U7") (pin "9") (pinfunction "D3_9") (pintype "bidirectional"))
    )
    (net (code "92") (name "unconnected-(U7-D4-Pad12)") (class "Default")
      (node (ref "U7") (pin "12") (pinfunction "D4_12") (pintype "bidirectional"))
    )
    (net (code "93") (name "unconnected-(U7-S3A-Pad11)") (class "Default")
      (node (ref "U7") (pin "11") (pinfunction "S3A_11") (pintype "bidirectional"))
    )
    (net (code "94") (name "unconnected-(U7-S3B-Pad10)") (class "Default")
      (node (ref "U7") (pin "10") (pinfunction "S3B_10") (pintype "bidirectional"))
    )
    (net (code "95") (name "unconnected-(U7-S4A-Pad14)") (class "Default")
      (node (ref "U7") (pin "14") (pinfunction "S4A_14") (pintype "bidirectional"))
    )
    (net (code "96") (name "unconnected-(U7-S4B-Pad13)") (class "Default")
      (node (ref "U7") (pin "13") (pinfunction "S4B_13") (pintype "bidirectional"))
    )
  )
)
